# Glove_V2.net
KiCad netlist of a schematic drawn in Altium Designer
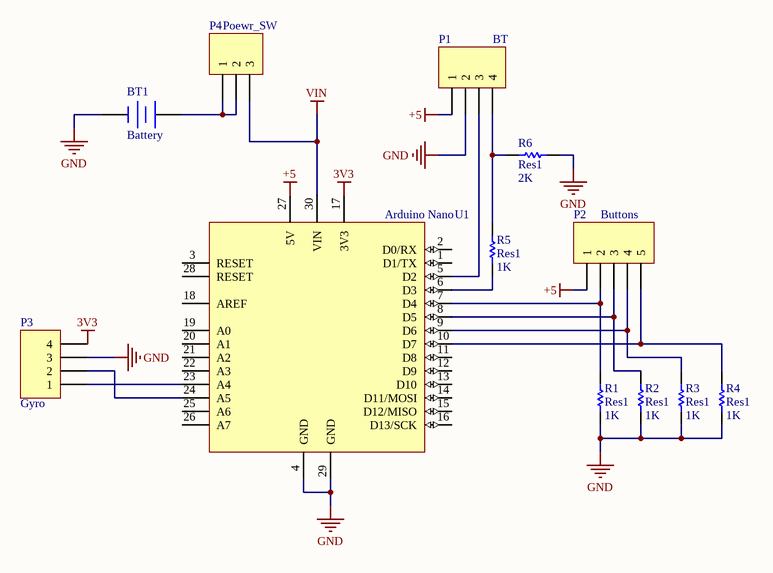
[diagram p0: Glove_V2.SchDoc]

(export (version "E")
  (design (tool "Eeschema 10.0.6"))
  (components
    (comp (ref "BT1")
      (value "Battery")
      (footprint "BAT-2")
      (description "Multicell Battery")
      (fields (field (name "PUBLISHER") "Altium Limited"))
      (libsource (lib "Miscellaneous Devices") (part "Battery"))
    )
    (comp (ref "P1")
      (value "BT")
      (footprint "HDR1X4H")
      (description "Header, 4-Pin, Right Angle")
      (fields (field (name "PUBLISHER") "Altium Limited"))
      (libsource (lib "Miscellaneous Connectors") (part "Header 4H"))
    )
    (comp (ref "P2")
      (value "Buttons")
      (footprint "HDR1X5H")
      (description "Header, 5-Pin, Right Angle")
      (fields (field (name "PUBLISHER") "Altium Limited"))
      (libsource (lib "Miscellaneous Connectors") (part "Header 5H"))
    )
    (comp (ref "P3")
      (value "Gyro")
      (footprint "HDR1X4H")
      (description "Header, 4-Pin, Right Angle")
      (fields (field (name "PUBLISHER") "Altium Limited"))
      (libsource (lib "") (part "Header 4H_1"))
    )
    (comp (ref "P4")
      (value "Poewr_SW")
      (footprint "HDR1X3")
      (description "Header, 3-Pin")
      (fields (field (name "PUBLISHER") "Altium Limited"))
      (libsource (lib "Miscellaneous Connectors") (part "Header 3"))
    )
    (comp (ref "R1")
      (value "Res1")
      (footprint "AXIAL-0.3")
      (description "Resistor")
      (fields (field (name "ALTIUM_VALUE") "1K") (field (name "PUBLISHER") "Altium Limited"))
      (libsource (lib "Miscellaneous Devices") (part "Res1"))
    )
    (comp (ref "R2")
      (value "Res1")
      (footprint "AXIAL-0.3")
      (description "Resistor")
      (fields (field (name "ALTIUM_VALUE") "1K") (field (name "PUBLISHER") "Altium Limited"))
      (libsource (lib "Miscellaneous Devices") (part "Res1"))
    )
    (comp (ref "R3")
      (value "Res1")
      (footprint "AXIAL-0.3")
      (description "Resistor")
      (fields (field (name "ALTIUM_VALUE") "1K") (field (name "PUBLISHER") "Altium Limited"))
      (libsource (lib "Miscellaneous Devices") (part "Res1"))
    )
    (comp (ref "R4")
      (value "Res1")
      (footprint "AXIAL-0.3")
      (description "Resistor")
      (fields (field (name "ALTIUM_VALUE") "1K") (field (name "PUBLISHER") "Altium Limited"))
      (libsource (lib "Miscellaneous Devices") (part "Res1"))
    )
    (comp (ref "R5")
      (value "Res1")
      (footprint "AXIAL-0.3")
      (description "Resistor")
      (fields (field (name "ALTIUM_VALUE") "1K") (field (name "PUBLISHER") "Altium Limited"))
      (libsource (lib "Miscellaneous Devices") (part "Res1"))
    )
    (comp (ref "R6")
      (value "Res1")
      (footprint "AXIAL-0.3")
      (description "Resistor")
      (fields (field (name "ALTIUM_VALUE") "2K") (field (name "PUBLISHER") "Altium Limited"))
      (libsource (lib "Miscellaneous Devices") (part "Res1"))
    )
    (comp (ref "U1")
      (value "Arduino Nano")
      (footprint "Arduino_Nano")
      (libsource (lib "Miscellaneous Devices") (part "Arduino Nano"))
    )
  )
  (nets
    (net (code "1") (name "+5") (class "Default")
      (node (ref "P1") (pin "1") (pinfunction "1_1") (pintype "passive"))
      (node (ref "P2") (pin "1") (pinfunction "1_1") (pintype "passive"))
      (node (ref "U1") (pin "27") (pinfunction "5V_27") (pintype "power_in"))
    )
    (net (code "2") (name "3V3") (class "Default")
      (node (ref "P3") (pin "4") (pinfunction "4_4") (pintype "passive"))
      (node (ref "U1") (pin "17") (pinfunction "3V3_17") (pintype "power_in"))
    )
    (net (code "3") (name "GND") (class "Default")
      (node (ref "BT1") (pin "2") (pinfunction "-_2") (pintype "passive"))
      (node (ref "P1") (pin "2") (pinfunction "2_2") (pintype "passive"))
      (node (ref "P3") (pin "3") (pinfunction "3_3") (pintype "passive"))
      (node (ref "R1") (pin "1") (pinfunction "1_1") (pintype "passive"))
      (node (ref "R2") (pin "1") (pinfunction "1_1") (pintype "passive"))
      (node (ref "R3") (pin "1") (pinfunction "1_1") (pintype "passive"))
      (node (ref "R4") (pin "1") (pinfunction "1_1") (pintype "passive"))
      (node (ref "R6") (pin "1") (pinfunction "1_1") (pintype "passive"))
      (node (ref "U1") (pin "29") (pinfunction "GND_29") (pintype "power_in"))
      (node (ref "U1") (pin "4") (pinfunction "GND_4") (pintype "power_in"))
    )
    (net (code "4") (name "Net-(BT1-+)") (class "Default")
      (node (ref "BT1") (pin "1") (pinfunction "+_1") (pintype "passive"))
      (node (ref "P4") (pin "1") (pinfunction "1_1") (pintype "passive"))
      (node (ref "P4") (pin "2") (pinfunction "2_2") (pintype "passive"))
    )
    (net (code "5") (name "Net-(P1-Pad4)") (class "Default")
      (node (ref "P1") (pin "4") (pinfunction "4_4") (pintype "passive"))
      (node (ref "R5") (pin "2") (pinfunction "2_2") (pintype "passive"))
      (node (ref "R6") (pin "2") (pinfunction "2_2") (pintype "passive"))
    )
    (net (code "6") (name "Net-(U1-A4)") (class "Default")
      (node (ref "P3") (pin "1") (pinfunction "1_1") (pintype "passive"))
      (node (ref "U1") (pin "23") (pinfunction "A4_23") (pintype "passive"))
    )
    (net (code "7") (name "Net-(U1-A5)") (class "Default")
      (node (ref "P3") (pin "2") (pinfunction "2_2") (pintype "passive"))
      (node (ref "U1") (pin "24") (pinfunction "A5_24") (pintype "passive"))
    )
    (net (code "8") (name "Net-(U1-D2)") (class "Default")
      (node (ref "P1") (pin "3") (pinfunction "3_3") (pintype "passive"))
      (node (ref "U1") (pin "5") (pinfunction "D2_5") (pintype "bidirectional"))
    )
    (net (code "9") (name "Net-(U1-D3)") (class "Default")
      (node (ref "R5") (pin "1") (pinfunction "1_1") (pintype "passive"))
      (node (ref "U1") (pin "6") (pinfunction "D3_6") (pintype "bidirectional"))
    )
    (net (code "10") (name "Net-(U1-D4)") (class "Default")
      (node (ref "P2") (pin "2") (pinfunction "2_2") (pintype "passive"))
      (node (ref "R1") (pin "2") (pinfunction "2_2") (pintype "passive"))
      (node (ref "U1") (pin "7") (pinfunction "D4_7") (pintype "bidirectional"))
    )
    (net (code "11") (name "Net-(U1-D5)") (class "Default")
      (node (ref "P2") (pin "3") (pinfunction "3_3") (pintype "passive"))
      (node (ref "R2") (pin "2") (pinfunction "2_2") (pintype "passive"))
      (node (ref "U1") (pin "8") (pinfunction "D5_8") (pintype "bidirectional"))
    )
    (net (code "12") (name "Net-(U1-D6)") (class "Default")
      (node (ref "P2") (pin "4") (pinfunction "4_4") (pintype "passive"))
      (node (ref "R3") (pin "2") (pinfunction "2_2") (pintype "passive"))
      (node (ref "U1") (pin "9") (pinfunction "D6_9") (pintype "bidirectional"))
    )
    (net (code "13") (name "Net-(U1-D7)") (class "Default")
      (node (ref "P2") (pin "5") (pinfunction "5_5") (pintype "passive"))
      (node (ref "R4") (pin "2") (pinfunction "2_2") (pintype "passive"))
      (node (ref "U1") (pin "10") (pinfunction "D7_10") (pintype "bidirectional"))
    )
    (net (code "14") (name "VIN") (class "Default")
      (node (ref "P4") (pin "3") (pinfunction "3_3") (pintype "passive"))
      (node (ref "U1") (pin "30") (pinfunction "VIN_30") (pintype "power_in"))
    )
    (net (code "15") (name "unconnected-(U1-A0-Pad19)") (class "Default")
      (node (ref "U1") (pin "19") (pinfunction "A0_19") (pintype "passive"))
    )
    (net (code "16") (name "unconnected-(U1-A1-Pad20)") (class "Default")
      (node (ref "U1") (pin "20") (pinfunction "A1_20") (pintype "passive"))
    )
    (net (code "17") (name "unconnected-(U1-A2-Pad21)") (class "Default")
      (node (ref "U1") (pin "21") (pinfunction "A2_21") (pintype "passive"))
    )
    (net (code "18") (name "unconnected-(U1-A3-Pad22)") (class "Default")
      (node (ref "U1") (pin "22") (pinfunction "A3_22") (pintype "passive"))
    )
    (net (code "19") (name "unconnected-(U1-A6-Pad25)") (class "Default")
      (node (ref "U1") (pin "25") (pinfunction "A6_25") (pintype "passive"))
    )
    (net (code "20") (name "unconnected-(U1-A7-Pad26)") (class "Default")
      (node (ref "U1") (pin "26") (pinfunction "A7_26") (pintype "passive"))
    )
    (net (code "21") (name "unconnected-(U1-AREF-Pad18)") (class "Default")
      (node (ref "U1") (pin "18") (pinfunction "AREF_18") (pintype "passive"))
    )
    (net (code "22") (name "unconnected-(U1-D0{slash}RX-Pad2)") (class "Default")
      (node (ref "U1") (pin "2") (pinfunction "D0/RX_2") (pintype "bidirectional"))
    )
    (net (code "23") (name "unconnected-(U1-D1{slash}TX-Pad1)") (class "Default")
      (node (ref "U1") (pin "1") (pinfunction "D1/TX_1") (pintype "bidirectional"))
    )
    (net (code "24") (name "unconnected-(U1-D8-Pad11)") (class "Default")
      (node (ref "U1") (pin "11") (pinfunction "D8_11") (pintype "bidirectional"))
    )
    (net (code "25") (name "unconnected-(U1-D9-Pad12)") (class "Default")
      (node (ref "U1") (pin "12") (pinfunction "D9_12") (pintype "bidirectional"))
    )
    (net (code "26") (name "unconnected-(U1-D10-Pad13)") (class "Default")
      (node (ref "U1") (pin "13") (pinfunction "D10_13") (pintype "bidirectional"))
    )
    (net (code "27") (name "unconnected-(U1-D11{slash}MOSI-Pad14)") (class "Default")
      (node (ref "U1") (pin "14") (pinfunction "D11/MOSI_14") (pintype "bidirectional"))
    )
    (net (code "28") (name "unconnected-(U1-D12{slash}MISO-Pad15)") (class "Default")
      (node (ref "U1") (pin "15") (pinfunction "D12/MISO_15") (pintype "bidirectional"))
    )
    (net (code "29") (name "unconnected-(U1-D13{slash}SCK-Pad16)") (class "Default")
      (node (ref "U1") (pin "16") (pinfunction "D13/SCK_16") (pintype "bidirectional"))
    )
    (net (code "30") (name "unconnected-(U1-RESET-Pad3)") (class "Default")
      (node (ref "U1") (pin "3") (pinfunction "RESET_3") (pintype "passive"))
    )
    (net (code "31") (name "unconnected-(U1-RESET-Pad28)") (class "Default")
      (node (ref "U1") (pin "28") (pinfunction "RESET_28") (pintype "passive"))
    )
  )
)
